# MiCS_Sensors.net
KiCad netlist of a schematic drawn in Altium Designer
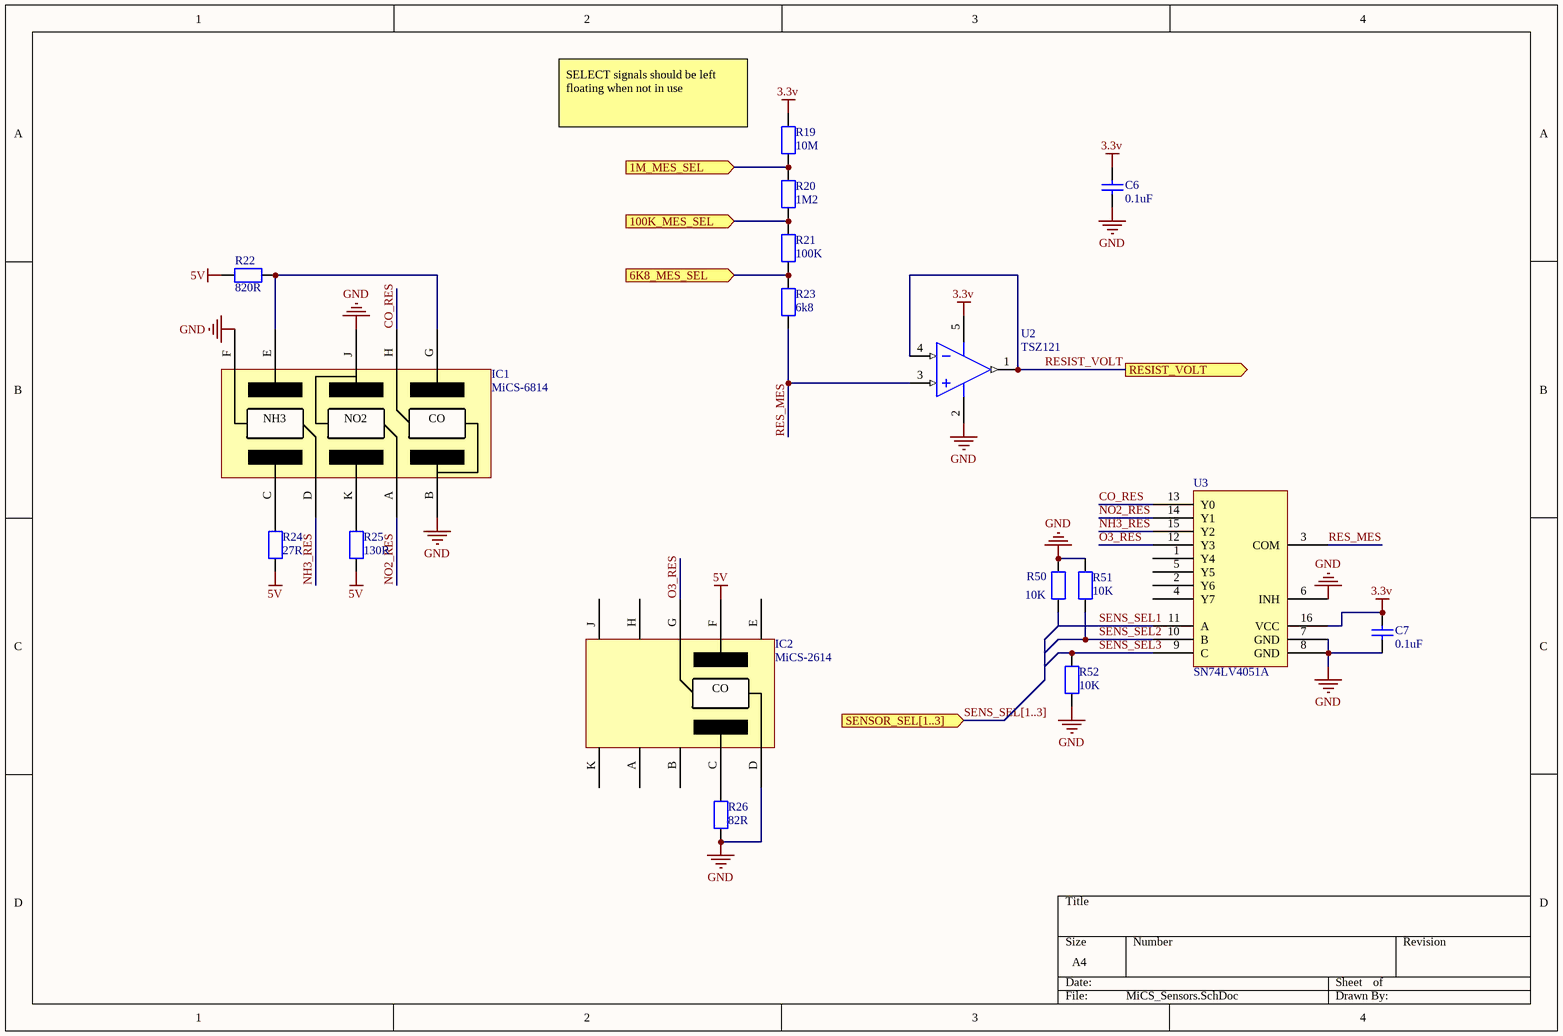
[diagram p0: MiCS_Sensors.SchDoc]

(export (version "E")
  (design (tool "Eeschema 10.0.6"))
  (components
    (comp (ref "C6")
      (value "0.1uF")
      (footprint "0603_CAP")
      (fields (field (name "Comment") "Capacitor"))
      (libsource (lib "Passive_comp") (part "Capacitor"))
    )
    (comp (ref "C7")
      (value "0.1uF")
      (footprint "0603_CAP")
      (fields (field (name "Comment") "Capacitor"))
      (libsource (lib "Passive_comp") (part "Capacitor"))
    )
    (comp (ref "IC1") (value "MiCS-6814") (footprint "MiCS") (libsource (lib "Sensors") (part "MiCS-6814")))
    (comp (ref "IC2") (value "MiCS-2614") (footprint "MiCS") (libsource (lib "Sensors") (part "MiCS-5524")))
    (comp (ref "R19")
      (value "10M")
      (footprint "0603_RES")
      (fields (field (name "Comment") "Resitor"))
      (libsource (lib "") (part "Resitor_1"))
    )
    (comp (ref "R20")
      (value "1M2")
      (footprint "0603_RES")
      (fields (field (name "Comment") "Resitor"))
      (libsource (lib "") (part "Resitor_1"))
    )
    (comp (ref "R21")
      (value "100K")
      (footprint "0603_RES")
      (fields (field (name "Comment") "Resitor"))
      (libsource (lib "") (part "Resitor_1"))
    )
    (comp (ref "R22")
      (value "820R")
      (footprint "0603_RES")
      (fields (field (name "Comment") "Resitor"))
      (libsource (lib "Passive_comp") (part "Resitor"))
    )
    (comp (ref "R23")
      (value "6k8")
      (footprint "0603_RES")
      (fields (field (name "Comment") "Resitor"))
      (libsource (lib "") (part "Resitor_1"))
    )
    (comp (ref "R24")
      (value "27R")
      (footprint "0603_RES")
      (fields (field (name "Comment") "Resitor"))
      (libsource (lib "") (part "Resitor_1"))
    )
    (comp (ref "R25")
      (value "130R")
      (footprint "0603_RES")
      (fields (field (name "Comment") "Resitor"))
      (libsource (lib "") (part "Resitor_1"))
    )
    (comp (ref "R26")
      (value "82R")
      (footprint "0603_RES")
      (fields (field (name "Comment") "Resitor"))
      (libsource (lib "") (part "Resitor_1"))
    )
    (comp (ref "R50")
      (value "10K")
      (footprint "0603_RES")
      (fields (field (name "Comment") "Resitor"))
      (libsource (lib "") (part "Resitor_1"))
    )
    (comp (ref "R51")
      (value "10K")
      (footprint "0603_RES")
      (fields (field (name "Comment") "Resitor"))
      (libsource (lib "") (part "Resitor_1"))
    )
    (comp (ref "R52")
      (value "10K")
      (footprint "0603_RES")
      (fields (field (name "Comment") "Resitor"))
      (libsource (lib "") (part "Resitor_1"))
    )
    (comp (ref "U2") (value "TSZ121") (footprint "SOT95P280X145-5M") (libsource (lib "stm") (part "TSZ121")))
    (comp (ref "U3")
      (value "SN74LV4051A")
      (footprint "TSOP65P640X120-16M")
      (description "Analog Multiplexer/Demultiplexer")
      (libsource (lib "Active_comp") (part "SN74LV4051A"))
    )
  )
  (nets
    (net (code "1") (name "/1M_MES_SEL") (class "Default")
      (node (ref "R19") (pin "1") (pinfunction "1_1") (pintype "passive"))
      (node (ref "R20") (pin "2") (pinfunction "2_2") (pintype "passive"))
    )
    (net (code "2") (name "/6K8_MES_SEL") (class "Default")
      (node (ref "R21") (pin "1") (pinfunction "1_1") (pintype "passive"))
      (node (ref "R23") (pin "2") (pinfunction "2_2") (pintype "passive"))
    )
    (net (code "3") (name "/100K_MES_SEL") (class "Default")
      (node (ref "R20") (pin "1") (pinfunction "1_1") (pintype "passive"))
      (node (ref "R21") (pin "2") (pinfunction "2_2") (pintype "passive"))
    )
    (net (code "4") (name "/CO_RES") (class "Default")
      (node (ref "IC1") (pin "H") (pinfunction "H_H") (pintype "passive"))
      (node (ref "U3") (pin "13") (pinfunction "Y0_13") (pintype "passive"))
    )
    (net (code "5") (name "/NH3_RES") (class "Default")
      (node (ref "IC1") (pin "D") (pinfunction "D_D") (pintype "passive"))
      (node (ref "U3") (pin "15") (pinfunction "Y2_15") (pintype "passive"))
    )
    (net (code "6") (name "/NO2_RES") (class "Default")
      (node (ref "IC1") (pin "A") (pinfunction "A_A") (pintype "passive"))
      (node (ref "U3") (pin "14") (pinfunction "Y1_14") (pintype "passive"))
    )
    (net (code "7") (name "/O3_RES") (class "Default")
      (node (ref "IC2") (pin "G") (pinfunction "G_G") (pintype "passive"))
      (node (ref "U3") (pin "12") (pinfunction "Y3_12") (pintype "passive"))
    )
    (net (code "8") (name "/RESIST_VOLT") (class "Default")
      (node (ref "U2") (pin "1") (pinfunction "OUT1_1") (pintype "output"))
      (node (ref "U2") (pin "4") (pinfunction "IN1-_4") (pintype "input"))
    )
    (net (code "9") (name "/RES_MES") (class "Default")
      (node (ref "R23") (pin "1") (pinfunction "1_1") (pintype "passive"))
      (node (ref "U2") (pin "3") (pinfunction "IN1+_3") (pintype "input"))
      (node (ref "U3") (pin "3") (pinfunction "COM_3") (pintype "passive"))
    )
    (net (code "10") (name "/SENS_SEL1") (class "Default")
      (node (ref "R50") (pin "1") (pinfunction "1_1") (pintype "passive"))
      (node (ref "U3") (pin "11") (pinfunction "A_11") (pintype "passive"))
    )
    (net (code "11") (name "/SENS_SEL2") (class "Default")
      (node (ref "R51") (pin "1") (pinfunction "1_1") (pintype "passive"))
      (node (ref "U3") (pin "10") (pinfunction "B_10") (pintype "passive"))
    )
    (net (code "12") (name "/SENS_SEL3") (class "Default")
      (node (ref "R52") (pin "2") (pinfunction "2_2") (pintype "passive"))
      (node (ref "U3") (pin "9") (pinfunction "C_9") (pintype "passive"))
    )
    (net (code "14") (name "3.3v") (class "Default")
      (node (ref "C6") (pin "2") (pinfunction "2_2") (pintype "passive"))
      (node (ref "C7") (pin "2") (pinfunction "2_2") (pintype "passive"))
      (node (ref "R19") (pin "2") (pinfunction "2_2") (pintype "passive"))
      (node (ref "U2") (pin "5") (pinfunction "V+_5") (pintype "power_in"))
      (node (ref "U3") (pin "16") (pinfunction "VCC_16") (pintype "passive"))
    )
    (net (code "15") (name "5V") (class "Default")
      (node (ref "IC2") (pin "F") (pinfunction "F_F") (pintype "passive"))
      (node (ref "R22") (pin "2") (pinfunction "2_2") (pintype "passive"))
      (node (ref "R24") (pin "1") (pinfunction "1_1") (pintype "passive"))
      (node (ref "R25") (pin "1") (pinfunction "1_1") (pintype "passive"))
    )
    (net (code "16") (name "GND") (class "Default")
      (node (ref "C6") (pin "1") (pinfunction "1_1") (pintype "passive"))
      (node (ref "C7") (pin "1") (pinfunction "1_1") (pintype "passive"))
      (node (ref "IC1") (pin "B") (pinfunction "B_B") (pintype "passive"))
      (node (ref "IC1") (pin "F") (pinfunction "F_F") (pintype "passive"))
      (node (ref "IC1") (pin "J") (pinfunction "J_J") (pintype "passive"))
      (node (ref "IC2") (pin "D") (pinfunction "D_D") (pintype "passive"))
      (node (ref "R26") (pin "1") (pinfunction "1_1") (pintype "passive"))
      (node (ref "R50") (pin "2") (pinfunction "2_2") (pintype "passive"))
      (node (ref "R51") (pin "2") (pinfunction "2_2") (pintype "passive"))
      (node (ref "R52") (pin "1") (pinfunction "1_1") (pintype "passive"))
      (node (ref "U2") (pin "2") (pinfunction "V-_2") (pintype "power_in"))
      (node (ref "U3") (pin "6") (pinfunction "INH_6") (pintype "passive"))
      (node (ref "U3") (pin "7") (pinfunction "GND_7") (pintype "passive"))
      (node (ref "U3") (pin "8") (pinfunction "GND_8") (pintype "passive"))
    )
    (net (code "17") (name "Net-(IC1-PadC)") (class "Default")
      (node (ref "IC1") (pin "C") (pinfunction "C_C") (pintype "passive"))
      (node (ref "R24") (pin "2") (pinfunction "2_2") (pintype "passive"))
    )
    (net (code "18") (name "Net-(IC1-PadE)") (class "Default")
      (node (ref "IC1") (pin "E") (pinfunction "E_E") (pintype "passive"))
      (node (ref "IC1") (pin "G") (pinfunction "G_G") (pintype "passive"))
      (node (ref "R22") (pin "1") (pinfunction "1_1") (pintype "passive"))
    )
    (net (code "19") (name "Net-(IC1-PadK)") (class "Default")
      (node (ref "IC1") (pin "K") (pinfunction "K_K") (pintype "passive"))
      (node (ref "R25") (pin "2") (pinfunction "2_2") (pintype "passive"))
    )
    (net (code "20") (name "Net-(IC2-PadC)") (class "Default")
      (node (ref "IC2") (pin "C") (pinfunction "C_C") (pintype "passive"))
      (node (ref "R26") (pin "2") (pinfunction "2_2") (pintype "passive"))
    )
    (net (code "21") (name "unconnected-(IC2-PadA)") (class "Default")
      (node (ref "IC2") (pin "A") (pinfunction "A_A") (pintype "passive"))
    )
    (net (code "22") (name "unconnected-(IC2-PadB)") (class "Default")
      (node (ref "IC2") (pin "B") (pinfunction "B_B") (pintype "passive"))
    )
    (net (code "23") (name "unconnected-(IC2-PadE)") (class "Default")
      (node (ref "IC2") (pin "E") (pinfunction "E_E") (pintype "passive"))
    )
    (net (code "24") (name "unconnected-(IC2-PadH)") (class "Default")
      (node (ref "IC2") (pin "H") (pinfunction "H_H") (pintype "passive"))
    )
    (net (code "25") (name "unconnected-(IC2-PadJ)") (class "Default")
      (node (ref "IC2") (pin "J") (pinfunction "J_J") (pintype "passive"))
    )
    (net (code "26") (name "unconnected-(IC2-PadK)") (class "Default")
      (node (ref "IC2") (pin "K") (pinfunction "K_K") (pintype "passive"))
    )
    (net (code "27") (name "unconnected-(U3-Y4-Pad1)") (class "Default")
      (node (ref "U3") (pin "1") (pinfunction "Y4_1") (pintype "passive"))
    )
    (net (code "28") (name "unconnected-(U3-Y5-Pad5)") (class "Default")
      (node (ref "U3") (pin "5") (pinfunction "Y5_5") (pintype "passive"))
    )
    (net (code "29") (name "unconnected-(U3-Y6-Pad2)") (class "Default")
      (node (ref "U3") (pin "2") (pinfunction "Y6_2") (pintype "passive"))
    )
    (net (code "30") (name "unconnected-(U3-Y7-Pad4)") (class "Default")
      (node (ref "U3") (pin "4") (pinfunction "Y7_4") (pintype "passive"))
    )
  )
)
